# AFE.net
KiCad netlist of a schematic drawn in Altium Designer
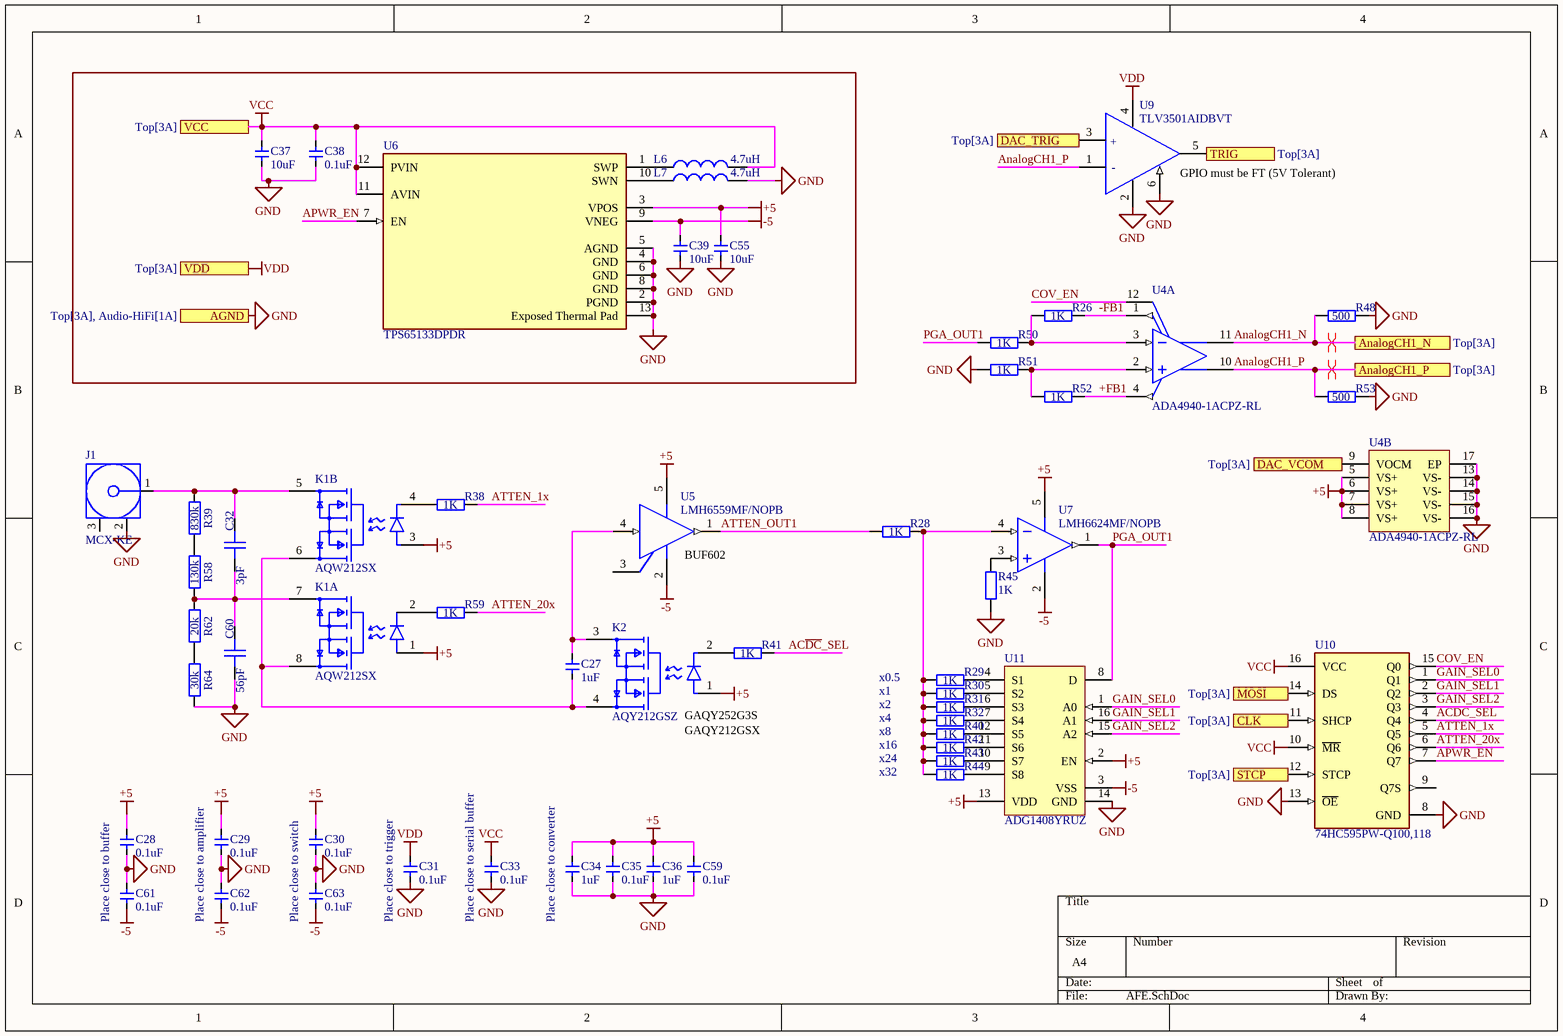
[diagram p0: AFE.SchDoc]

(export (version "E")
  (design (tool "Eeschema 10.0.6"))
  (components
    (comp (ref "C27")
      (value "1uF")
      (footprint "0402-C")
      (description "Capacitor")
      (libsource (lib "MyPcbLib") (part "电容-0402"))
    )
    (comp (ref "C28")
      (value "0.1uF")
      (footprint "0402-C")
      (description "Capacitor")
      (libsource (lib "MyPcbLib") (part "电容-0402"))
    )
    (comp (ref "C29")
      (value "0.1uF")
      (footprint "0402-C")
      (description "Capacitor")
      (libsource (lib "MyPcbLib") (part "电容-0402"))
    )
    (comp (ref "C30")
      (value "0.1uF")
      (footprint "0402-C")
      (description "Capacitor")
      (libsource (lib "MyPcbLib") (part "电容-0402"))
    )
    (comp (ref "C31")
      (value "0.1uF")
      (footprint "0402-C")
      (description "Capacitor")
      (libsource (lib "MyPcbLib") (part "电容-0402"))
    )
    (comp (ref "C32")
      (value "3pF")
      (footprint "0402-C")
      (fields
        (field (name "MANUFACTURER") "Kyocera AVX")
        (field (name "MANUFACTURER PART NUMBER") "600F241FT250XT")
      )
      (libsource (lib "DSO") (part "CAP 240pF 250V C0G 0805"))
    )
    (comp (ref "C33")
      (value "0.1uF")
      (footprint "0402-C")
      (description "Capacitor")
      (libsource (lib "MyPcbLib") (part "电容-0402"))
    )
    (comp (ref "C34")
      (value "1uF")
      (footprint "0402-C")
      (description "Capacitor")
      (libsource (lib "MyPcbLib") (part "电容-0402"))
    )
    (comp (ref "C35")
      (value "0.1uF")
      (footprint "0402-C")
      (description "Capacitor")
      (libsource (lib "MyPcbLib") (part "电容-0402"))
    )
    (comp (ref "C36")
      (value "1uF")
      (footprint "0402-C")
      (description "Capacitor")
      (libsource (lib "MyPcbLib") (part "电容-0402"))
    )
    (comp (ref "C37")
      (value "10uF")
      (footprint "0402-C")
      (description "Capacitor")
      (libsource (lib "MyPcbLib") (part "电容-0402"))
    )
    (comp (ref "C38")
      (value "0.1uF")
      (footprint "0402-C")
      (description "Capacitor")
      (libsource (lib "MyPcbLib") (part "电容-0402"))
    )
    (comp (ref "C39")
      (value "10uF")
      (footprint "0402-C")
      (description "Capacitor")
      (libsource (lib "MyPcbLib") (part "电容-0402"))
    )
    (comp (ref "C55")
      (value "10uF")
      (footprint "0402-C")
      (description "Capacitor")
      (libsource (lib "MyPcbLib") (part "电容-0402"))
    )
    (comp (ref "C59")
      (value "0.1uF")
      (footprint "0402-C")
      (description "Capacitor")
      (libsource (lib "MyPcbLib") (part "电容-0402"))
    )
    (comp (ref "C60")
      (value "56pF")
      (footprint "0402-C")
      (fields
        (field (name "MANUFACTURER") "Kyocera AVX")
        (field (name "MANUFACTURER PART NUMBER") "600F241FT250XT")
      )
      (libsource (lib "DSO") (part "CAP 240pF 250V C0G 0805"))
    )
    (comp (ref "C61")
      (value "0.1uF")
      (footprint "0402-C")
      (description "Capacitor")
      (libsource (lib "MyPcbLib") (part "电容-0402"))
    )
    (comp (ref "C62")
      (value "0.1uF")
      (footprint "0402-C")
      (description "Capacitor")
      (libsource (lib "MyPcbLib") (part "电容-0402"))
    )
    (comp (ref "C63")
      (value "0.1uF")
      (footprint "0402-C")
      (description "Capacitor")
      (libsource (lib "MyPcbLib") (part "电容-0402"))
    )
    (comp (ref "J1")
      (value "MCX-KE")
      (footprint "60612202111308")
      (description "60612202111308 WR-MCX_MCX PCB End Launch Jack")
      (libsource (lib "Altium Content Vault") (part "Jack_2GND"))
    )
    (comp (ref "K1")
      (value "AQW212SX")
      (footprint "FP-AQW212SX-MFG")
      (description "AQW212SX Mosfet Relay, Dpst-No, 0.4A, 60V, Sop-8 Rohs Compliant: Yes")
      (libsource (lib "Altium Content Vault") (part "63004cd1d3b581ddcd2b6fb3ac05930"))
    )
    (comp (ref "K2")
      (value "AQY212GSZ")
      (footprint "FP-AQY212GSZ-MFG")
      (description "AQY212GSZ Relay Ssr 50MA 1.5V Dc-in 1A 60V Ac/dc-out 4-PIN Sop T/r")
      (libsource (lib "Altium Content Vault") (part "39108d2c2fe9c6c4263f1aa8ae40286"))
    )
    (comp (ref "L6")
      (value "4.7uH")
      (footprint "L0805")
      (description "贴片小功率电感")
      (libsource (lib "0.1 - 电阻-电容-电感-保险丝-晶振-晶体-磁珠-电位器-法拉电容-馈通电容") (part "L"))
    )
    (comp (ref "L7")
      (value "4.7uH")
      (footprint "L0805")
      (description "贴片小功率电感")
      (libsource (lib "0.1 - 电阻-电容-电感-保险丝-晶振-晶体-磁珠-电位器-法拉电容-馈通电容") (part "L"))
    )
    (comp (ref "R26")
      (value "1K")
      (footprint "0402-R")
      (description "贴片电阻")
      (libsource (lib "0.1 - 电阻-电容-电感-晶振-晶体-磁珠-电位器") (part "R"))
    )
    (comp (ref "R28")
      (value "1K")
      (footprint "0402-R")
      (description "贴片电阻")
      (libsource (lib "0.1 - 电阻-电容-电感-晶振-晶体-磁珠-电位器") (part "R"))
    )
    (comp (ref "R29")
      (value "1K")
      (footprint "0402-R")
      (description "贴片电阻")
      (libsource (lib "0.1 - 电阻-电容-电感-晶振-晶体-磁珠-电位器") (part "R"))
    )
    (comp (ref "R30")
      (value "1K")
      (footprint "0402-R")
      (description "贴片电阻")
      (libsource (lib "0.1 - 电阻-电容-电感-晶振-晶体-磁珠-电位器") (part "R"))
    )
    (comp (ref "R31")
      (value "1K")
      (footprint "0402-R")
      (description "贴片电阻")
      (libsource (lib "0.1 - 电阻-电容-电感-晶振-晶体-磁珠-电位器") (part "R"))
    )
    (comp (ref "R32")
      (value "1K")
      (footprint "0402-R")
      (description "贴片电阻")
      (libsource (lib "0.1 - 电阻-电容-电感-晶振-晶体-磁珠-电位器") (part "R"))
    )
    (comp (ref "R38")
      (value "1K")
      (footprint "0402-R")
      (description "贴片电阻")
      (libsource (lib "0.1 - 电阻-电容-电感-晶振-晶体-磁珠-电位器") (part "R"))
    )
    (comp (ref "R39")
      (value "830k")
      (footprint "0402-R")
      (fields
        (field (name "TOLERANCE") "1%")
        (field (name "MANUFACTURER") "Yageo")
        (field (name "MANUFACTURER PART NUMBER") "RC0402FR-0720KL")
      )
      (libsource (lib "DSO") (part "RES 20K OHM 1% 1/16W 0402"))
    )
    (comp (ref "R40")
      (value "1K")
      (footprint "0402-R")
      (description "贴片电阻")
      (libsource (lib "0.1 - 电阻-电容-电感-晶振-晶体-磁珠-电位器") (part "R"))
    )
    (comp (ref "R41")
      (value "1K")
      (footprint "0402-R")
      (description "贴片电阻")
      (libsource (lib "0.1 - 电阻-电容-电感-晶振-晶体-磁珠-电位器") (part "R"))
    )
    (comp (ref "R42")
      (value "1K")
      (footprint "0402-R")
      (description "贴片电阻")
      (libsource (lib "0.1 - 电阻-电容-电感-晶振-晶体-磁珠-电位器") (part "R"))
    )
    (comp (ref "R43")
      (value "1K")
      (footprint "0402-R")
      (description "贴片电阻")
      (libsource (lib "0.1 - 电阻-电容-电感-晶振-晶体-磁珠-电位器") (part "R"))
    )
    (comp (ref "R44")
      (value "1K")
      (footprint "0402-R")
      (description "贴片电阻")
      (libsource (lib "0.1 - 电阻-电容-电感-晶振-晶体-磁珠-电位器") (part "R"))
    )
    (comp (ref "R45")
      (value "1K")
      (footprint "0402-R")
      (description "贴片电阻")
      (libsource (lib "0.1 - 电阻-电容-电感-晶振-晶体-磁珠-电位器") (part "R"))
    )
    (comp (ref "R48")
      (value "500")
      (footprint "0402-R")
      (description "贴片电阻")
      (libsource (lib "0.1 - 电阻-电容-电感-晶振-晶体-磁珠-电位器") (part "R"))
    )
    (comp (ref "R50")
      (value "1K")
      (footprint "0402-R")
      (description "贴片电阻")
      (libsource (lib "0.1 - 电阻-电容-电感-晶振-晶体-磁珠-电位器") (part "R"))
    )
    (comp (ref "R51")
      (value "1K")
      (footprint "0402-R")
      (description "贴片电阻")
      (libsource (lib "0.1 - 电阻-电容-电感-晶振-晶体-磁珠-电位器") (part "R"))
    )
    (comp (ref "R52")
      (value "1K")
      (footprint "0402-R")
      (description "贴片电阻")
      (libsource (lib "0.1 - 电阻-电容-电感-晶振-晶体-磁珠-电位器") (part "R"))
    )
    (comp (ref "R53")
      (value "500")
      (footprint "0402-R")
      (description "贴片电阻")
      (libsource (lib "0.1 - 电阻-电容-电感-晶振-晶体-磁珠-电位器") (part "R"))
    )
    (comp (ref "R58")
      (value "130k")
      (footprint "0402-R")
      (fields
        (field (name "TOLERANCE") "1%")
        (field (name "MANUFACTURER") "Yageo")
        (field (name "MANUFACTURER PART NUMBER") "RC0402FR-0720KL")
      )
      (libsource (lib "DSO") (part "RES 20K OHM 1% 1/16W 0402"))
    )
    (comp (ref "R59")
      (value "1K")
      (footprint "0402-R")
      (description "贴片电阻")
      (libsource (lib "0.1 - 电阻-电容-电感-晶振-晶体-磁珠-电位器") (part "R"))
    )
    (comp (ref "R62")
      (value "20k")
      (footprint "0402-R")
      (fields
        (field (name "TOLERANCE") "1%")
        (field (name "MANUFACTURER") "Yageo")
        (field (name "MANUFACTURER PART NUMBER") "RC0402FR-0720KL")
      )
      (libsource (lib "DSO") (part "RES 20K OHM 1% 1/16W 0402"))
    )
    (comp (ref "R64")
      (value "30k")
      (footprint "0402-R")
      (fields
        (field (name "TOLERANCE") "1%")
        (field (name "MANUFACTURER") "Yageo")
        (field (name "MANUFACTURER PART NUMBER") "RC0402FR-0720KL")
      )
      (libsource (lib "DSO") (part "RES 20K OHM 1% 1/16W 0402"))
    )
    (comp (ref "U4")
      (value "ADA4940-1ACPZ-RL")
      (footprint "ADI-CP-16-2_M")
      (fields (field (name "MANUFACTURER") "Analog Devices"))
      (libsource (lib "Altium Content Vault") (part "ADI-ADA4940-CP-16-2"))
    )
    (comp (ref "U5")
      (value "LMH6559MF/NOPB")
      (footprint "DBV0005A_L")
      (description "High-Speed, Closed-Loop Buffer, 5-pin SOT-23, Pb-Free")
      (fields (field (name "MANUFACTURER") "Texas Instruments"))
      (libsource (lib "Altium Content Vault") (part "AMP-BUF-LMH6559-5"))
    )
    (comp (ref "U6")
      (value "TPS65133DPDR")
      (footprint "FP-DPD0012A-MFG")
      (description "IC REG AMOLED DISPL 2OUT 12WSON")
      (libsource (lib "Altium Content Vault") (part "cb0e1e7d26f86b63177112bdd55f499"))
    )
    (comp (ref "U7")
      (value "LMH6624MF/NOPB")
      (footprint "DBV0005A_L")
      (description "Single/ Dual Ultra Low Noise Wideband Operational Amplifier, 5-pin SOT-23, Pb-Free")
      (fields (field (name "MANUFACTURER") "Texas Instruments"))
      (libsource (lib "Altium Content Vault") (part "AMP-OPA-LM7121-5"))
    )
    (comp (ref "U9")
      (value "TLV3501AIDBVT")
      (footprint "FP-DBV0006A-MFG")
      (description "IC COMP 4.5NS R-R HS SOT23-6")
      (fields
        (field (name "MANUFACTURER") "Texas Instruments")
        (field (name "OCTOPART") "https://octopart.com/tlv3501aidbvt-texas+instruments-428399")
      )
      (libsource (lib "Altium Content Vault") (part "0ecce7053b56ec2eec74f62614cfafa"))
    )
    (comp (ref "U10")
      (value "74HC595PW-Q100,118")
      (footprint "FP-SOT403-1-MFG")
      (description "IC SHIFT REGISTER 8BIT 16TSSOP")
      (fields
        (field (name "MANUFACTURER") "Nexperia")
        (field (name "OCTOPART") "https://octopart.com/74hc595pw-q100%2C118-nexperia-78737379")
      )
      (libsource (lib "Altium Content Vault") (part "35014dcb5ee7218ec7bb80311b7c79e"))
    )
    (comp (ref "U11")
      (value "ADG1408YRUZ")
      (footprint "ADI-RU-16_N")
      (description "4 Ohm Ron, 8-Channel +/-15 V / +12 V / +/-5 V iCMOS Multiplexer, 16-pin SOP (RU-16), Tube")
      (fields (field (name "MANUFACTURER") "Analog Devices"))
      (libsource (lib "Altium Content Vault") (part "ADI-ADG1408-RU-16"))
    )
  )
  (nets
    (net (code "1") (name "+5") (class "Default")
      (node (ref "C28") (pin "2") (pinfunction "2_2") (pintype "passive"))
      (node (ref "C29") (pin "2") (pinfunction "2_2") (pintype "passive"))
      (node (ref "C30") (pin "2") (pinfunction "2_2") (pintype "passive"))
      (node (ref "C34") (pin "2") (pinfunction "2_2") (pintype "passive"))
      (node (ref "C35") (pin "2") (pinfunction "2_2") (pintype "passive"))
      (node (ref "C36") (pin "2") (pinfunction "2_2") (pintype "passive"))
      (node (ref "C55") (pin "2") (pinfunction "2_2") (pintype "passive"))
      (node (ref "C59") (pin "2") (pinfunction "2_2") (pintype "passive"))
      (node (ref "K1") (pin "1") (pinfunction "1_ANODE_1") (pintype "passive"))
      (node (ref "K1") (pin "3") (pinfunction "2_ANODE_3") (pintype "passive"))
      (node (ref "K2") (pin "1") (pinfunction "A_1") (pintype "passive"))
      (node (ref "U11") (pin "13") (pinfunction "VDD_13") (pintype "power_in"))
      (node (ref "U11") (pin "2") (pinfunction "EN_2") (pintype "input"))
      (node (ref "U4") (pin "5") (pinfunction "VS+_5") (pintype "power_in"))
      (node (ref "U4") (pin "6") (pinfunction "VS+_6") (pintype "power_in"))
      (node (ref "U4") (pin "7") (pinfunction "VS+_7") (pintype "power_in"))
      (node (ref "U4") (pin "8") (pinfunction "VS+_8") (pintype "power_in"))
      (node (ref "U5") (pin "5") (pinfunction "VCC_5") (pintype "power_in"))
      (node (ref "U6") (pin "3") (pinfunction "VPOS_3") (pintype "power_in"))
      (node (ref "U7") (pin "5") (pinfunction "V+_5") (pintype "power_in"))
    )
    (net (code "2") (name "-5") (class "Default")
      (node (ref "C39") (pin "2") (pinfunction "2_2") (pintype "passive"))
      (node (ref "C61") (pin "1") (pinfunction "1_1") (pintype "passive"))
      (node (ref "C62") (pin "1") (pinfunction "1_1") (pintype "passive"))
      (node (ref "C63") (pin "1") (pinfunction "1_1") (pintype "passive"))
      (node (ref "U11") (pin "3") (pinfunction "VSS_3") (pintype "power_in"))
      (node (ref "U5") (pin "2") (pinfunction "VEE_2") (pintype "power_in"))
      (node (ref "U6") (pin "9") (pinfunction "VNEG_9") (pintype "power_in"))
      (node (ref "U7") (pin "2") (pinfunction "V-_2") (pintype "power_in"))
    )
    (net (code "3") (name "/+FB1") (class "Default")
      (node (ref "R52") (pin "1") (pinfunction "1_1") (pintype "passive"))
      (node (ref "U4") (pin "4") (pinfunction "FB+_4") (pintype "output"))
    )
    (net (code "4") (name "/-FB1") (class "Default")
      (node (ref "R26") (pin "1") (pinfunction "1_1") (pintype "passive"))
      (node (ref "U4") (pin "1") (pinfunction "FB-_1") (pintype "output"))
    )
    (net (code "5") (name "/AC~{DC}_SEL") (class "Default")
      (node (ref "R41") (pin "1") (pinfunction "1_1") (pintype "passive"))
      (node (ref "U10") (pin "4") (pinfunction "Q4_4") (pintype "output"))
    )
    (net (code "6") (name "/APWR_EN") (class "Default")
      (node (ref "U10") (pin "7") (pinfunction "Q7_7") (pintype "output"))
      (node (ref "U6") (pin "7") (pinfunction "EN_7") (pintype "input"))
    )
    (net (code "7") (name "/ATTEN_1x") (class "Default")
      (node (ref "R38") (pin "1") (pinfunction "1_1") (pintype "passive"))
      (node (ref "U10") (pin "5") (pinfunction "Q5_5") (pintype "output"))
    )
    (net (code "8") (name "/ATTEN_20x") (class "Default")
      (node (ref "R59") (pin "1") (pinfunction "1_1") (pintype "passive"))
      (node (ref "U10") (pin "6") (pinfunction "Q6_6") (pintype "output"))
    )
    (net (code "9") (name "/ATTEN_OUT1") (class "Default")
      (node (ref "R28") (pin "2") (pinfunction "2_2") (pintype "passive"))
      (node (ref "U5") (pin "1") (pinfunction "OUT_1") (pintype "output"))
    )
    (net (code "10") (name "/AnalogCH1_N") (class "Default")
      (node (ref "R48") (pin "2") (pinfunction "2_2") (pintype "passive"))
      (node (ref "U4") (pin "11") (pinfunction "OUT-_11") (pintype "tri_state"))
    )
    (net (code "11") (name "/AnalogCH1_P") (class "Default")
      (node (ref "R53") (pin "2") (pinfunction "2_2") (pintype "passive"))
      (node (ref "U4") (pin "10") (pinfunction "OUT+_10") (pintype "tri_state"))
      (node (ref "U9") (pin "1") (pinfunction "-IN_1") (pintype "tri_state"))
    )
    (net (code "12") (name "/CLK") (class "Default")
      (node (ref "U10") (pin "11") (pinfunction "SHCP_11") (pintype "input"))
    )
    (net (code "13") (name "/COV_EN") (class "Default")
      (node (ref "U10") (pin "15") (pinfunction "Q0_15") (pintype "output"))
      (node (ref "U4") (pin "12") (pinfunction "~{DISABLE}_12") (pintype "passive"))
    )
    (net (code "14") (name "/DAC_TRIG") (class "Default")
      (node (ref "U9") (pin "3") (pinfunction "+IN_3") (pintype "tri_state"))
    )
    (net (code "15") (name "/DAC_VCOM") (class "Default")
      (node (ref "U4") (pin "9") (pinfunction "VOCM_9") (pintype "power_in"))
    )
    (net (code "16") (name "/GAIN_SEL0") (class "Default")
      (node (ref "U10") (pin "1") (pinfunction "Q1_1") (pintype "output"))
      (node (ref "U11") (pin "1") (pinfunction "A0_1") (pintype "input"))
    )
    (net (code "17") (name "/GAIN_SEL1") (class "Default")
      (node (ref "U10") (pin "2") (pinfunction "Q2_2") (pintype "output"))
      (node (ref "U11") (pin "16") (pinfunction "A1_16") (pintype "input"))
    )
    (net (code "18") (name "/GAIN_SEL2") (class "Default")
      (node (ref "U10") (pin "3") (pinfunction "Q3_3") (pintype "output"))
      (node (ref "U11") (pin "15") (pinfunction "A2_15") (pintype "input"))
    )
    (net (code "19") (name "/MOSI") (class "Default")
      (node (ref "U10") (pin "14") (pinfunction "DS_14") (pintype "input"))
    )
    (net (code "20") (name "/PGA_OUT1") (class "Default")
      (node (ref "R50") (pin "2") (pinfunction "2_2") (pintype "passive"))
      (node (ref "U11") (pin "8") (pinfunction "D_8") (pintype "passive"))
      (node (ref "U7") (pin "1") (pinfunction "OUT_1") (pintype "output"))
    )
    (net (code "21") (name "/STCP") (class "Default")
      (node (ref "U10") (pin "12") (pinfunction "STCP_12") (pintype "input"))
    )
    (net (code "22") (name "/TRIG") (class "Default")
      (node (ref "U9") (pin "5") (pinfunction "OUT_5") (pintype "passive"))
    )
    (net (code "23") (name "GND") (class "Default")
      (node (ref "C28") (pin "1") (pinfunction "1_1") (pintype "passive"))
      (node (ref "C29") (pin "1") (pinfunction "1_1") (pintype "passive"))
      (node (ref "C30") (pin "1") (pinfunction "1_1") (pintype "passive"))
      (node (ref "C31") (pin "2") (pinfunction "2_2") (pintype "passive"))
      (node (ref "C33") (pin "2") (pinfunction "2_2") (pintype "passive"))
      (node (ref "C34") (pin "1") (pinfunction "1_1") (pintype "passive"))
      (node (ref "C35") (pin "1") (pinfunction "1_1") (pintype "passive"))
      (node (ref "C36") (pin "1") (pinfunction "1_1") (pintype "passive"))
      (node (ref "C37") (pin "1") (pinfunction "1_1") (pintype "passive"))
      (node (ref "C38") (pin "1") (pinfunction "1_1") (pintype "passive"))
      (node (ref "C39") (pin "1") (pinfunction "1_1") (pintype "passive"))
      (node (ref "C55") (pin "1") (pinfunction "1_1") (pintype "passive"))
      (node (ref "C59") (pin "1") (pinfunction "1_1") (pintype "passive"))
      (node (ref "C60") (pin "1") (pinfunction "1_1") (pintype "passive"))
      (node (ref "C61") (pin "2") (pinfunction "2_2") (pintype "passive"))
      (node (ref "C62") (pin "2") (pinfunction "2_2") (pintype "passive"))
      (node (ref "C63") (pin "2") (pinfunction "2_2") (pintype "passive"))
      (node (ref "J1") (pin "2") (pinfunction "GND_2") (pintype "passive"))
      (node (ref "L7") (pin "2") (pinfunction "2_2") (pintype "passive"))
      (node (ref "R45") (pin "2") (pinfunction "2_2") (pintype "passive"))
      (node (ref "R48") (pin "1") (pinfunction "1_1") (pintype "passive"))
      (node (ref "R51") (pin "2") (pinfunction "2_2") (pintype "passive"))
      (node (ref "R53") (pin "1") (pinfunction "1_1") (pintype "passive"))
      (node (ref "R64") (pin "1") (pinfunction "1_1") (pintype "passive"))
      (node (ref "U10") (pin "13") (pinfunction "~{OE}_13") (pintype "input"))
      (node (ref "U10") (pin "8") (pinfunction "GND_8") (pintype "power_in"))
      (node (ref "U11") (pin "14") (pinfunction "GND_14") (pintype "power_in"))
      (node (ref "U4") (pin "13") (pinfunction "VS-_13") (pintype "power_in"))
      (node (ref "U4") (pin "14") (pinfunction "VS-_14") (pintype "power_in"))
      (node (ref "U4") (pin "15") (pinfunction "VS-_15") (pintype "power_in"))
      (node (ref "U4") (pin "16") (pinfunction "VS-_16") (pintype "power_in"))
      (node (ref "U4") (pin "17") (pinfunction "EP_17") (pintype "power_in"))
      (node (ref "U6") (pin "13") (pinfunction "Exposed_Thermal_Pad_13") (pintype "power_in"))
      (node (ref "U6") (pin "2") (pinfunction "PGND_2") (pintype "power_in"))
      (node (ref "U6") (pin "4") (pinfunction "GND_4") (pintype "power_in"))
      (node (ref "U6") (pin "5") (pinfunction "AGND_5") (pintype "power_in"))
      (node (ref "U6") (pin "6") (pinfunction "GND_6") (pintype "power_in"))
      (node (ref "U6") (pin "8") (pinfunction "GND_8") (pintype "power_in"))
      (node (ref "U9") (pin "2") (pinfunction "V-_2") (pintype "power_in"))
      (node (ref "U9") (pin "6") (pinfunction "SHDN_6") (pintype "input"))
    )
    (net (code "24") (name "Net-(J1-Signal)") (class "Default")
      (node (ref "C32") (pin "2") (pinfunction "2_2") (pintype "passive"))
      (node (ref "J1") (pin "1") (pinfunction "Signal_1") (pintype "passive"))
      (node (ref "K1") (pin "5") (pinfunction "2_1_DRAIN_5") (pintype "passive"))
      (node (ref "R39") (pin "2") (pinfunction "2_2") (pintype "passive"))
    )
    (net (code "25") (name "Net-(K1A-1_1_DRAIN)") (class "Default")
      (node (ref "C32") (pin "1") (pinfunction "1_1") (pintype "passive"))
      (node (ref "C60") (pin "2") (pinfunction "2_2") (pintype "passive"))
      (node (ref "K1") (pin "7") (pinfunction "1_1_DRAIN_7") (pintype "passive"))
      (node (ref "R58") (pin "1") (pinfunction "1_1") (pintype "passive"))
      (node (ref "R62") (pin "2") (pinfunction "2_2") (pintype "passive"))
    )
    (net (code "26") (name "Net-(K1A-1_2_DRAIN)") (class "Default")
      (node (ref "C27") (pin "2") (pinfunction "2_2") (pintype "passive"))
      (node (ref "K1") (pin "6") (pinfunction "2_2_DRAIN_6") (pintype "passive"))
      (node (ref "K1") (pin "8") (pinfunction "1_2_DRAIN_8") (pintype "passive"))
      (node (ref "K2") (pin "4") (pinfunction "2_DRAIN_4") (pintype "passive"))
    )
    (net (code "27") (name "Net-(K1A-1_CATHODE)") (class "Default")
      (node (ref "K1") (pin "2") (pinfunction "1_CATHODE_2") (pintype "passive"))
      (node (ref "R59") (pin "2") (pinfunction "2_2") (pintype "passive"))
    )
    (net (code "28") (name "Net-(K1B-2_CATHODE)") (class "Default")
      (node (ref "K1") (pin "4") (pinfunction "2_CATHODE_4") (pintype "passive"))
      (node (ref "R38") (pin "2") (pinfunction "2_2") (pintype "passive"))
    )
    (net (code "29") (name "Net-(K2-1_DRAIN)") (class "Default")
      (node (ref "C27") (pin "1") (pinfunction "1_1") (pintype "passive"))
      (node (ref "K2") (pin "3") (pinfunction "1_DRAIN_3") (pintype "passive"))
      (node (ref "U5") (pin "4") (pinfunction "IN_4") (pintype "input"))
    )
    (net (code "30") (name "Net-(K2-C)") (class "Default")
      (node (ref "K2") (pin "2") (pinfunction "C_2") (pintype "passive"))
      (node (ref "R41") (pin "2") (pinfunction "2_2") (pintype "passive"))
    )
    (net (code "31") (name "Net-(R39-Pad1)") (class "Default")
      (node (ref "R39") (pin "1") (pinfunction "1_1") (pintype "passive"))
      (node (ref "R58") (pin "2") (pinfunction "2_2") (pintype "passive"))
    )
    (net (code "32") (name "Net-(R62-Pad1)") (class "Default")
      (node (ref "R62") (pin "1") (pinfunction "1_1") (pintype "passive"))
      (node (ref "R64") (pin "2") (pinfunction "2_2") (pintype "passive"))
    )
    (net (code "33") (name "Net-(U4A-IN+)") (class "Default")
      (node (ref "R51") (pin "1") (pinfunction "1_1") (pintype "passive"))
      (node (ref "R52") (pin "2") (pinfunction "2_2") (pintype "passive"))
      (node (ref "U4") (pin "2") (pinfunction "IN+_2") (pintype "input"))
    )
    (net (code "34") (name "Net-(U4A-IN-)") (class "Default")
      (node (ref "R26") (pin "2") (pinfunction "2_2") (pintype "passive"))
      (node (ref "R50") (pin "1") (pinfunction "1_1") (pintype "passive"))
      (node (ref "U4") (pin "3") (pinfunction "IN-_3") (pintype "input"))
    )
    (net (code "35") (name "Net-(U6-SWN)") (class "Default")
      (node (ref "L7") (pin "1") (pinfunction "1_1") (pintype "passive"))
      (node (ref "U6") (pin "10") (pinfunction "SWN_10") (pintype "power_in"))
    )
    (net (code "36") (name "Net-(U6-SWP)") (class "Default")
      (node (ref "L6") (pin "1") (pinfunction "1_1") (pintype "passive"))
      (node (ref "U6") (pin "1") (pinfunction "SWP_1") (pintype "power_in"))
    )
    (net (code "37") (name "Net-(U7-IN+)") (class "Default")
      (node (ref "R45") (pin "1") (pinfunction "1_1") (pintype "passive"))
      (node (ref "U7") (pin "3") (pinfunction "IN+_3") (pintype "input"))
    )
    (net (code "38") (name "Net-(U7-IN-)") (class "Default")
      (node (ref "R28") (pin "1") (pinfunction "1_1") (pintype "passive"))
      (node (ref "R29") (pin "2") (pinfunction "2_2") (pintype "passive"))
      (node (ref "R30") (pin "2") (pinfunction "2_2") (pintype "passive"))
      (node (ref "R31") (pin "2") (pinfunction "2_2") (pintype "passive"))
      (node (ref "R32") (pin "2") (pinfunction "2_2") (pintype "passive"))
      (node (ref "R40") (pin "2") (pinfunction "2_2") (pintype "passive"))
      (node (ref "R42") (pin "2") (pinfunction "2_2") (pintype "passive"))
      (node (ref "R43") (pin "2") (pinfunction "2_2") (pintype "passive"))
      (node (ref "R44") (pin "2") (pinfunction "2_2") (pintype "passive"))
      (node (ref "U7") (pin "4") (pinfunction "IN-_4") (pintype "input"))
    )
    (net (code "39") (name "Net-(U11-S1)") (class "Default")
      (node (ref "R29") (pin "1") (pinfunction "1_1") (pintype "passive"))
      (node (ref "U11") (pin "4") (pinfunction "S1_4") (pintype "passive"))
    )
    (net (code "40") (name "Net-(U11-S2)") (class "Default")
      (node (ref "R30") (pin "1") (pinfunction "1_1") (pintype "passive"))
      (node (ref "U11") (pin "5") (pinfunction "S2_5") (pintype "passive"))
    )
    (net (code "41") (name "Net-(U11-S3)") (class "Default")
      (node (ref "R31") (pin "1") (pinfunction "1_1") (pintype "passive"))
      (node (ref "U11") (pin "6") (pinfunction "S3_6") (pintype "passive"))
    )
    (net (code "42") (name "Net-(U11-S4)") (class "Default")
      (node (ref "R32") (pin "1") (pinfunction "1_1") (pintype "passive"))
      (node (ref "U11") (pin "7") (pinfunction "S4_7") (pintype "passive"))
    )
    (net (code "43") (name "Net-(U11-S5)") (class "Default")
      (node (ref "R40") (pin "1") (pinfunction "1_1") (pintype "passive"))
      (node (ref "U11") (pin "12") (pinfunction "S5_12") (pintype "passive"))
    )
    (net (code "44") (name "Net-(U11-S6)") (class "Default")
      (node (ref "R42") (pin "1") (pinfunction "1_1") (pintype "passive"))
      (node (ref "U11") (pin "11") (pinfunction "S6_11") (pintype "passive"))
    )
    (net (code "45") (name "Net-(U11-S7)") (class "Default")
      (node (ref "R43") (pin "1") (pinfunction "1_1") (pintype "passive"))
      (node (ref "U11") (pin "10") (pinfunction "S7_10") (pintype "passive"))
    )
    (net (code "46") (name "Net-(U11-S8)") (class "Default")
      (node (ref "R44") (pin "1") (pinfunction "1_1") (pintype "passive"))
      (node (ref "U11") (pin "9") (pinfunction "S8_9") (pintype "passive"))
    )
    (net (code "47") (name "VCC") (class "Default")
      (node (ref "C33") (pin "1") (pinfunction "1_1") (pintype "passive"))
      (node (ref "C37") (pin "2") (pinfunction "2_2") (pintype "passive"))
      (node (ref "C38") (pin "2") (pinfunction "2_2") (pintype "passive"))
      (node (ref "L6") (pin "2") (pinfunction "2_2") (pintype "passive"))
      (node (ref "U10") (pin "10") (pinfunction "~{MR}_10") (pintype "input"))
      (node (ref "U10") (pin "16") (pinfunction "VCC_16") (pintype "power_in"))
      (node (ref "U6") (pin "11") (pinfunction "AVIN_11") (pintype "power_in"))
      (node (ref "U6") (pin "12") (pinfunction "PVIN_12") (pintype "power_in"))
    )
    (net (code "48") (name "VDD") (class "Default")
      (node (ref "C31") (pin "1") (pinfunction "1_1") (pintype "passive"))
      (node (ref "U9") (pin "4") (pinfunction "V+_4") (pintype "power_in"))
    )
    (net (code "49") (name "unconnected-(J1-GND-Pad3)") (class "Default")
      (node (ref "J1") (pin "3") (pinfunction "GND_3") (pintype "passive"))
    )
    (net (code "50") (name "unconnected-(U5-NC-Pad3)") (class "Default")
      (node (ref "U5") (pin "3") (pinfunction "NC_3") (pintype "passive"))
    )
    (net (code "51") (name "unconnected-(U10-Q7S-Pad9)") (class "Default")
      (node (ref "U10") (pin "9") (pinfunction "Q7S_9") (pintype "output"))
    )
  )
)
